# INDUCTANCE_METER.net
KiCad netlist of a schematic drawn in Altium Designer
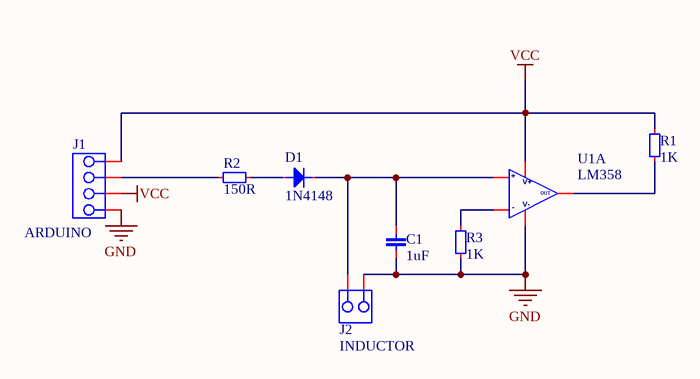
[diagram p0: INDUCTANCE_METER.SchDoc]

(export (version "E")
  (design (tool "Eeschema 10.0.6"))
  (components
    (comp (ref "C1")
      (value "1uF")
      (footprint "CAP_DISC_4x3_YL")
      (libsource (lib "MyAltiumLibrary") (part "Capacitors(Disc)"))
    )
    (comp (ref "D1")
      (value "1N4148")
      (footprint "DO-204AH-RD")
      (libsource (lib "MyAltiumLibrary") (part "Diode-1N4148"))
    )
    (comp (ref "J1")
      (value "ARDUINO")
      (footprint "HEADER-MALE-04PINS-2.54MM")
      (libsource (lib "MyAltiumLibrary") (part "HEADER-MALE-04PINS-2.54MM"))
    )
    (comp (ref "J2")
      (value "INDUCTOR")
      (footprint "DG306-5.0-02P-12-00AH")
      (libsource (lib "MyAltiumLibrary") (part "DG306-5.0-02P-12-00AH"))
    )
    (comp (ref "R1") (value "1K") (footprint "RES-0.25W-H-CF") (libsource (lib "") (part "Resistors THD_1")))
    (comp (ref "R2")
      (value "150R")
      (footprint "RES-0.25W-H-CF")
      (libsource (lib "MyAltiumLibrary") (part "Resistors THD"))
    )
    (comp (ref "R3") (value "1K") (footprint "RES-0.25W-H-CF") (libsource (lib "") (part "Resistors THD_1")))
    (comp (ref "U1")
      (value "LM358")
      (footprint "DIP-8")
      (libsource (lib "MyAltiumLibrary") (part "Oamp-LM358"))
    )
  )
  (nets
    (net (code "1") (name "GND") (class "Default")
      (node (ref "C1") (pin "1") (pinfunction "1_1") (pintype "passive"))
      (node (ref "J1") (pin "4") (pinfunction "4_4") (pintype "passive"))
      (node (ref "J2") (pin "2") (pinfunction "2_2") (pintype "passive"))
      (node (ref "R3") (pin "1") (pinfunction "1_1") (pintype "passive"))
      (node (ref "U1") (pin "4") (pinfunction "4_4") (pintype "power_in"))
    )
    (net (code "2") (name "Net-(D1-Pad1)") (class "Default")
      (node (ref "D1") (pin "1") (pinfunction "1_1") (pintype "passive"))
      (node (ref "R2") (pin "1") (pinfunction "1_1") (pintype "passive"))
    )
    (net (code "3") (name "Net-(J1-Pad2)") (class "Default")
      (node (ref "J1") (pin "2") (pinfunction "2_2") (pintype "passive"))
      (node (ref "R2") (pin "2") (pinfunction "2_2") (pintype "passive"))
    )
    (net (code "4") (name "Net-(U1A-+)") (class "Default")
      (node (ref "C1") (pin "2") (pinfunction "2_2") (pintype "passive"))
      (node (ref "D1") (pin "2") (pinfunction "2_2") (pintype "passive"))
      (node (ref "J2") (pin "1") (pinfunction "1_1") (pintype "passive"))
      (node (ref "U1") (pin "3") (pinfunction "+_3") (pintype "passive"))
    )
    (net (code "5") (name "Net-(U1A--)") (class "Default")
      (node (ref "R3") (pin "2") (pinfunction "2_2") (pintype "passive"))
      (node (ref "U1") (pin "2") (pinfunction "-_2") (pintype "passive"))
    )
    (net (code "6") (name "Net-(U1A-OUT)") (class "Default")
      (node (ref "R1") (pin "1") (pinfunction "1_1") (pintype "passive"))
      (node (ref "U1") (pin "1") (pinfunction "OUT_1") (pintype "passive"))
    )
    (net (code "7") (name "VCC") (class "Default")
      (node (ref "J1") (pin "1") (pinfunction "1_1") (pintype "passive"))
      (node (ref "J1") (pin "3") (pinfunction "3_3") (pintype "passive"))
      (node (ref "R1") (pin "2") (pinfunction "2_2") (pintype "passive"))
      (node (ref "U1") (pin "8") (pinfunction "8_8") (pintype "power_in"))
    )
  )
)
